# SONOFFPROG.net
KiCad netlist of a schematic drawn in EAGLE
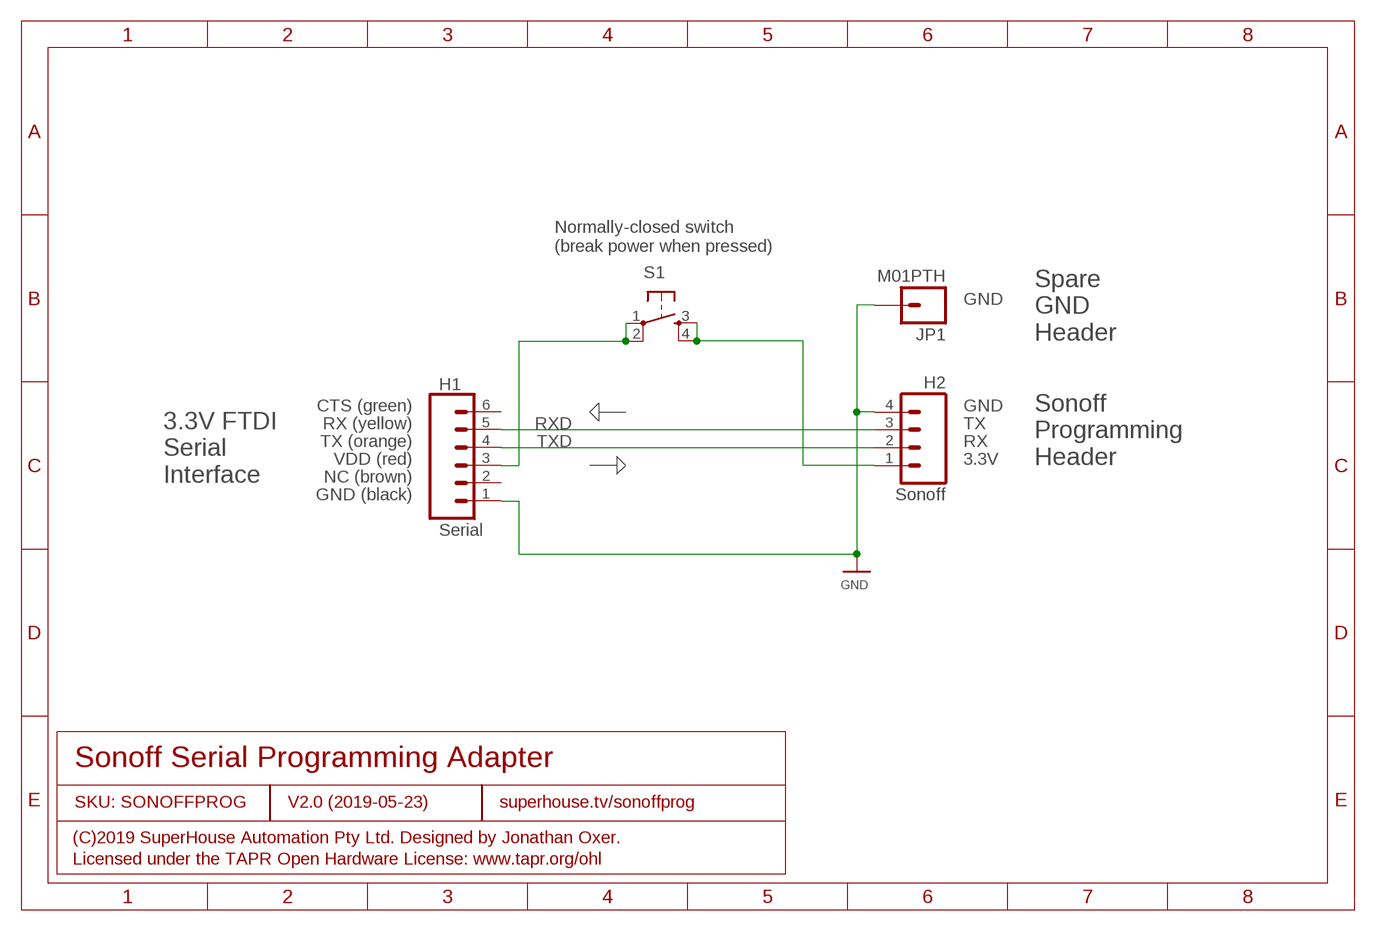
[diagram p0: schematic, sheet 1]

(export (version "E")
  (design (tool "Eeschema 10.0.6"))
  (components
    (comp (ref "H1")
      (value "Serial")
      (footprint "eagle-import:1X06")
      (libsource (lib "eagle-import") (part "M06SIP"))
    )
    (comp (ref "H2")
      (value "Sonoff")
      (footprint "eagle-import:1X04")
      (libsource (lib "eagle-import") (part "M04PTH"))
    )
    (comp (ref "JP1")
      (value "M01PTH")
      (footprint "eagle-import:1X01")
      (libsource (lib "eagle-import") (part "M01PTH"))
    )
    (comp (ref "S1")
      (value "TAC_SWITCHPTH")
      (footprint "eagle-import:TACTILE-PTH")
      (libsource (lib "eagle-import") (part "TAC_SWITCHPTH"))
    )
  )
  (nets
    (net (code "1") (name "/RXD") (class "Default")
      (node (ref "H1") (pin "5") (pinfunction "5_5") (pintype "passive"))
      (node (ref "H2") (pin "3") (pinfunction "3_3") (pintype "passive"))
    )
    (net (code "2") (name "/TXD") (class "Default")
      (node (ref "H1") (pin "4") (pinfunction "4_4") (pintype "passive"))
      (node (ref "H2") (pin "2") (pinfunction "2_2") (pintype "passive"))
    )
    (net (code "3") (name "GND") (class "Default")
      (node (ref "H1") (pin "1") (pinfunction "1_1") (pintype "passive"))
      (node (ref "H2") (pin "4") (pinfunction "4_4") (pintype "passive"))
      (node (ref "JP1") (pin "1") (pinfunction "1_1") (pintype "passive"))
    )
    (net (code "4") (name "Net-(H1-Pad3)") (class "Default")
      (node (ref "H1") (pin "3") (pinfunction "3_3") (pintype "passive"))
      (node (ref "S1") (pin "1") (pinfunction "1_1") (pintype "passive"))
      (node (ref "S1") (pin "2") (pinfunction "2_2") (pintype "passive"))
    )
    (net (code "5") (name "Net-(H2-Pad1)") (class "Default")
      (node (ref "H2") (pin "1") (pinfunction "1_1") (pintype "passive"))
      (node (ref "S1") (pin "3") (pinfunction "3_3") (pintype "passive"))
      (node (ref "S1") (pin "4") (pinfunction "4_4") (pintype "passive"))
    )
    (net (code "6") (name "unconnected-(H1-Pad2)") (class "Default")
      (node (ref "H1") (pin "2") (pinfunction "2_2") (pintype "passive"))
    )
    (net (code "7") (name "unconnected-(H1-Pad6)") (class "Default")
      (node (ref "H1") (pin "6") (pinfunction "6_6") (pintype "passive"))
    )
  )
)
